# M121X.net
KiCad netlist of a schematic drawn in EAGLE
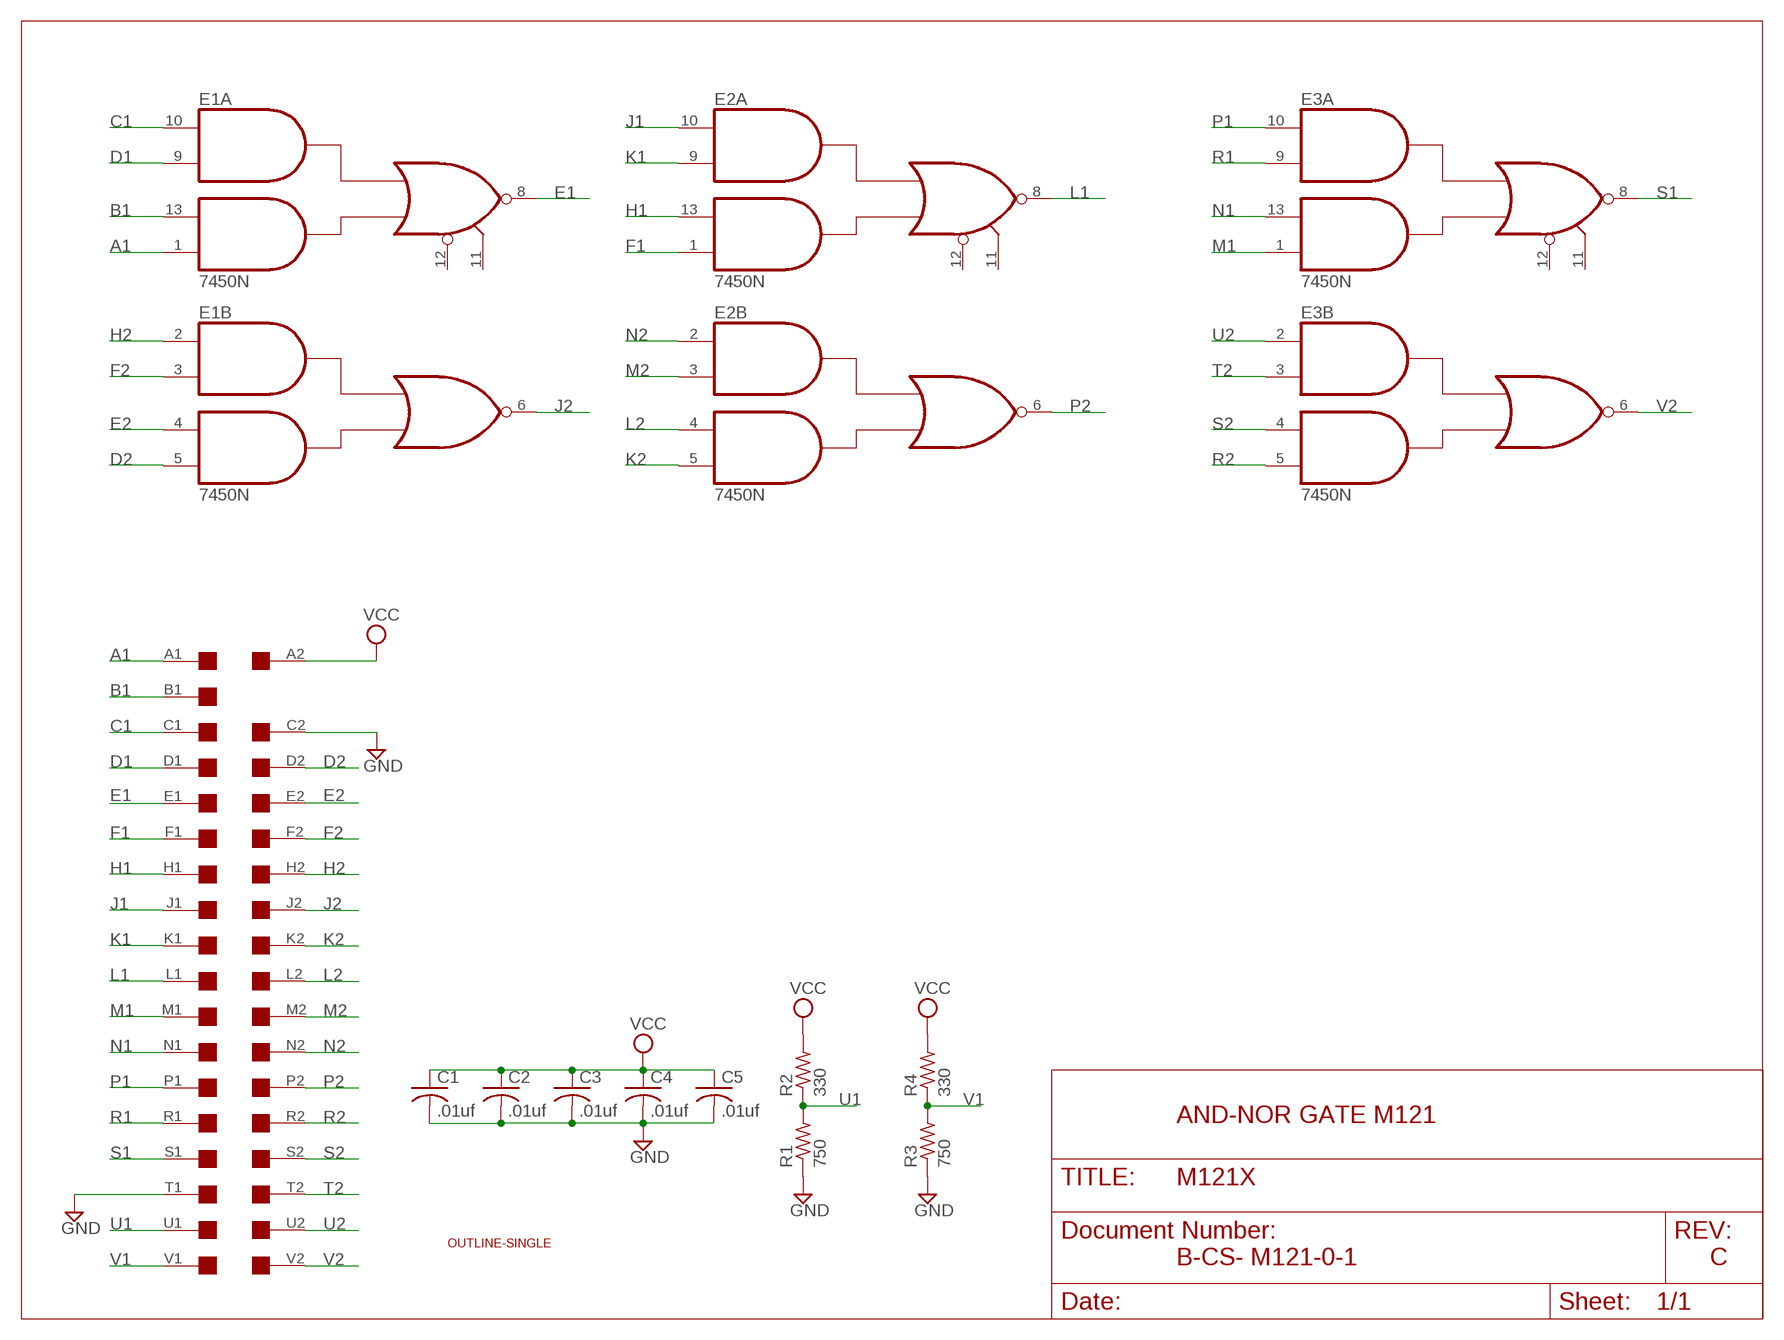
[diagram p0: schematic, sheet 1]

(export (version "E")
  (design (tool "Eeschema 10.0.6"))
  (components
    (comp (ref "C1")
      (value ".01uf")
      (footprint "eagle-import:C050-025X075")
      (libsource (lib "eagle-import") (part "C-US050-025X075"))
    )
    (comp (ref "C2")
      (value ".01uf")
      (footprint "eagle-import:C050-025X075")
      (libsource (lib "eagle-import") (part "C-US050-025X075"))
    )
    (comp (ref "C3")
      (value ".01uf")
      (footprint "eagle-import:C050-025X075")
      (libsource (lib "eagle-import") (part "C-US050-025X075"))
    )
    (comp (ref "C4")
      (value ".01uf")
      (footprint "eagle-import:C050-025X075")
      (libsource (lib "eagle-import") (part "C-US050-025X075"))
    )
    (comp (ref "C5")
      (value ".01uf")
      (footprint "eagle-import:C050-025X075")
      (libsource (lib "eagle-import") (part "C-US050-025X075"))
    )
    (comp (ref "E1")
      (value "7450N")
      (footprint "eagle-import:DIL14")
      (libsource (lib "eagle-import") (part "7450N"))
    )
    (comp (ref "E2")
      (value "7450N")
      (footprint "eagle-import:DIL14")
      (libsource (lib "eagle-import") (part "7450N"))
    )
    (comp (ref "E3")
      (value "7450N")
      (footprint "eagle-import:DIL14")
      (libsource (lib "eagle-import") (part "7450N"))
    )
    (comp (ref "R1")
      (value "750")
      (footprint "eagle-import:0207_10")
      (libsource (lib "eagle-import") (part "R-US_0207/10"))
    )
    (comp (ref "R2")
      (value "330")
      (footprint "eagle-import:0207_10")
      (libsource (lib "eagle-import") (part "R-US_0207/10"))
    )
    (comp (ref "R3")
      (value "750")
      (footprint "eagle-import:0207_10")
      (libsource (lib "eagle-import") (part "R-US_0207/10"))
    )
    (comp (ref "R4")
      (value "330")
      (footprint "eagle-import:0207_10")
      (libsource (lib "eagle-import") (part "R-US_0207/10"))
    )
    (comp (ref "U$1")
      (value "OUTLINE-SINGLE")
      (footprint "eagle-import:SINGLE")
      (libsource (lib "eagle-import") (part "OUTLINE-SINGLE"))
    )
    (comp (ref "U$4")
      (value "SINGLE")
      (footprint "eagle-import:EDGE-CON2")
      (libsource (lib "eagle-import") (part "SINGLE"))
    )
  )
  (nets
    (net (code "1") (name "/A1") (class "Default")
      (node (ref "E1") (pin "1") (pinfunction "I4_1") (pintype "input"))
      (node (ref "U$4") (pin "A1") (pinfunction "1_A1") (pintype "bidirectional"))
    )
    (net (code "2") (name "/B1") (class "Default")
      (node (ref "E1") (pin "13") (pinfunction "I3_13") (pintype "input"))
      (node (ref "U$4") (pin "B1") (pinfunction "1_B1") (pintype "bidirectional"))
    )
    (net (code "3") (name "/C1") (class "Default")
      (node (ref "E1") (pin "10") (pinfunction "I1_10") (pintype "input"))
      (node (ref "U$4") (pin "C1") (pinfunction "1_C1") (pintype "bidirectional"))
    )
    (net (code "4") (name "/D1") (class "Default")
      (node (ref "E1") (pin "9") (pinfunction "I2_9") (pintype "input"))
      (node (ref "U$4") (pin "D1") (pinfunction "1_D1") (pintype "bidirectional"))
    )
    (net (code "5") (name "/D2") (class "Default")
      (node (ref "E1") (pin "5") (pinfunction "I4_5") (pintype "input"))
      (node (ref "U$4") (pin "D2") (pinfunction "1_D2") (pintype "bidirectional"))
    )
    (net (code "6") (name "/E1") (class "Default")
      (node (ref "E1") (pin "8") (pinfunction "O_8") (pintype "output"))
      (node (ref "U$4") (pin "E1") (pinfunction "1_E1") (pintype "bidirectional"))
    )
    (net (code "7") (name "/E2") (class "Default")
      (node (ref "E1") (pin "4") (pinfunction "I3_4") (pintype "input"))
      (node (ref "U$4") (pin "E2") (pinfunction "1_E2") (pintype "bidirectional"))
    )
    (net (code "8") (name "/F1") (class "Default")
      (node (ref "E2") (pin "1") (pinfunction "I4_1") (pintype "input"))
      (node (ref "U$4") (pin "F1") (pinfunction "1_F1") (pintype "bidirectional"))
    )
    (net (code "9") (name "/F2") (class "Default")
      (node (ref "E1") (pin "3") (pinfunction "I2_3") (pintype "input"))
      (node (ref "U$4") (pin "F2") (pinfunction "1_F2") (pintype "bidirectional"))
    )
    (net (code "10") (name "/H1") (class "Default")
      (node (ref "E2") (pin "13") (pinfunction "I3_13") (pintype "input"))
      (node (ref "U$4") (pin "H1") (pinfunction "1_H1") (pintype "bidirectional"))
    )
    (net (code "11") (name "/H2") (class "Default")
      (node (ref "E1") (pin "2") (pinfunction "I1_2") (pintype "input"))
      (node (ref "U$4") (pin "H2") (pinfunction "1_H2") (pintype "bidirectional"))
    )
    (net (code "12") (name "/J1") (class "Default")
      (node (ref "E2") (pin "10") (pinfunction "I1_10") (pintype "input"))
      (node (ref "U$4") (pin "J1") (pinfunction "1_J1") (pintype "bidirectional"))
    )
    (net (code "13") (name "/J2") (class "Default")
      (node (ref "E1") (pin "6") (pinfunction "O_6") (pintype "output"))
      (node (ref "U$4") (pin "J2") (pinfunction "1_J2") (pintype "bidirectional"))
    )
    (net (code "14") (name "/K1") (class "Default")
      (node (ref "E2") (pin "9") (pinfunction "I2_9") (pintype "input"))
      (node (ref "U$4") (pin "K1") (pinfunction "1_K1") (pintype "bidirectional"))
    )
    (net (code "15") (name "/K2") (class "Default")
      (node (ref "E2") (pin "5") (pinfunction "I4_5") (pintype "input"))
      (node (ref "U$4") (pin "K2") (pinfunction "1_K2") (pintype "bidirectional"))
    )
    (net (code "16") (name "/L1") (class "Default")
      (node (ref "E2") (pin "8") (pinfunction "O_8") (pintype "output"))
      (node (ref "U$4") (pin "L1") (pinfunction "1_L1") (pintype "bidirectional"))
    )
    (net (code "17") (name "/L2") (class "Default")
      (node (ref "E2") (pin "4") (pinfunction "I3_4") (pintype "input"))
      (node (ref "U$4") (pin "L2") (pinfunction "1_L2") (pintype "bidirectional"))
    )
    (net (code "18") (name "/M1") (class "Default")
      (node (ref "E3") (pin "1") (pinfunction "I4_1") (pintype "input"))
      (node (ref "U$4") (pin "M1") (pinfunction "1_M1") (pintype "bidirectional"))
    )
    (net (code "19") (name "/M2") (class "Default")
      (node (ref "E2") (pin "3") (pinfunction "I2_3") (pintype "input"))
      (node (ref "U$4") (pin "M2") (pinfunction "1_M2") (pintype "bidirectional"))
    )
    (net (code "20") (name "/N1") (class "Default")
      (node (ref "E3") (pin "13") (pinfunction "I3_13") (pintype "input"))
      (node (ref "U$4") (pin "N1") (pinfunction "1_N1") (pintype "bidirectional"))
    )
    (net (code "21") (name "/N2") (class "Default")
      (node (ref "E2") (pin "2") (pinfunction "I1_2") (pintype "input"))
      (node (ref "U$4") (pin "N2") (pinfunction "1_N2") (pintype "bidirectional"))
    )
    (net (code "22") (name "/P1") (class "Default")
      (node (ref "E3") (pin "10") (pinfunction "I1_10") (pintype "input"))
      (node (ref "U$4") (pin "P1") (pinfunction "1_P1") (pintype "bidirectional"))
    )
    (net (code "23") (name "/P2") (class "Default")
      (node (ref "E2") (pin "6") (pinfunction "O_6") (pintype "output"))
      (node (ref "U$4") (pin "P2") (pinfunction "1_P2") (pintype "bidirectional"))
    )
    (net (code "24") (name "/R1") (class "Default")
      (node (ref "E3") (pin "9") (pinfunction "I2_9") (pintype "input"))
      (node (ref "U$4") (pin "R1") (pinfunction "1_R1") (pintype "bidirectional"))
    )
    (net (code "25") (name "/R2") (class "Default")
      (node (ref "E3") (pin "5") (pinfunction "I4_5") (pintype "input"))
      (node (ref "U$4") (pin "R2") (pinfunction "1_R2") (pintype "bidirectional"))
    )
    (net (code "26") (name "/S1") (class "Default")
      (node (ref "E3") (pin "8") (pinfunction "O_8") (pintype "output"))
      (node (ref "U$4") (pin "S1") (pinfunction "1_S1") (pintype "bidirectional"))
    )
    (net (code "27") (name "/S2") (class "Default")
      (node (ref "E3") (pin "4") (pinfunction "I3_4") (pintype "input"))
      (node (ref "U$4") (pin "S2") (pinfunction "1_S2") (pintype "bidirectional"))
    )
    (net (code "28") (name "/T2") (class "Default")
      (node (ref "E3") (pin "3") (pinfunction "I2_3") (pintype "input"))
      (node (ref "U$4") (pin "T2") (pinfunction "1_T2") (pintype "bidirectional"))
    )
    (net (code "29") (name "/U1") (class "Default")
      (node (ref "R1") (pin "2") (pinfunction "2_2") (pintype "passive"))
      (node (ref "R2") (pin "1") (pinfunction "1_1") (pintype "passive"))
      (node (ref "U$4") (pin "U1") (pinfunction "1_U1") (pintype "bidirectional"))
    )
    (net (code "30") (name "/U2") (class "Default")
      (node (ref "E3") (pin "2") (pinfunction "I1_2") (pintype "input"))
      (node (ref "U$4") (pin "U2") (pinfunction "1_U2") (pintype "bidirectional"))
    )
    (net (code "31") (name "/V1") (class "Default")
      (node (ref "R3") (pin "2") (pinfunction "2_2") (pintype "passive"))
      (node (ref "R4") (pin "1") (pinfunction "1_1") (pintype "passive"))
      (node (ref "U$4") (pin "V1") (pinfunction "1_V1") (pintype "bidirectional"))
    )
    (net (code "32") (name "/V2") (class "Default")
      (node (ref "E3") (pin "6") (pinfunction "O_6") (pintype "output"))
      (node (ref "U$4") (pin "V2") (pinfunction "1_V2") (pintype "bidirectional"))
    )
    (net (code "33") (name "GND") (class "Default")
      (node (ref "C1") (pin "2") (pinfunction "2_2") (pintype "passive"))
      (node (ref "C2") (pin "2") (pinfunction "2_2") (pintype "passive"))
      (node (ref "C3") (pin "2") (pinfunction "2_2") (pintype "passive"))
      (node (ref "C4") (pin "2") (pinfunction "2_2") (pintype "passive"))
      (node (ref "C5") (pin "2") (pinfunction "2_2") (pintype "passive"))
      (node (ref "R1") (pin "1") (pinfunction "1_1") (pintype "passive"))
      (node (ref "R3") (pin "1") (pinfunction "1_1") (pintype "passive"))
      (node (ref "U$4") (pin "C2") (pinfunction "1_C2") (pintype "bidirectional"))
      (node (ref "U$4") (pin "T1") (pinfunction "1_T1") (pintype "bidirectional"))
    )
    (net (code "34") (name "VCC") (class "Default")
      (node (ref "C1") (pin "1") (pinfunction "1_1") (pintype "passive"))
      (node (ref "C2") (pin "1") (pinfunction "1_1") (pintype "passive"))
      (node (ref "C3") (pin "1") (pinfunction "1_1") (pintype "passive"))
      (node (ref "C4") (pin "1") (pinfunction "1_1") (pintype "passive"))
      (node (ref "C5") (pin "1") (pinfunction "1_1") (pintype "passive"))
      (node (ref "R2") (pin "2") (pinfunction "2_2") (pintype "passive"))
      (node (ref "R4") (pin "2") (pinfunction "2_2") (pintype "passive"))
      (node (ref "U$4") (pin "A2") (pinfunction "1_A2") (pintype "bidirectional"))
    )
    (net (code "35") (name "unconnected-(E1A-I5-Pad12)") (class "Default")
      (node (ref "E1") (pin "12") (pinfunction "I5_12") (pintype "passive"))
    )
    (net (code "36") (name "unconnected-(E1A-I6-Pad11)") (class "Default")
      (node (ref "E1") (pin "11") (pinfunction "I6_11") (pintype "passive"))
    )
    (net (code "37") (name "unconnected-(E2A-I5-Pad12)") (class "Default")
      (node (ref "E2") (pin "12") (pinfunction "I5_12") (pintype "passive"))
    )
    (net (code "38") (name "unconnected-(E2A-I6-Pad11)") (class "Default")
      (node (ref "E2") (pin "11") (pinfunction "I6_11") (pintype "passive"))
    )
    (net (code "39") (name "unconnected-(E3A-I5-Pad12)") (class "Default")
      (node (ref "E3") (pin "12") (pinfunction "I5_12") (pintype "passive"))
    )
    (net (code "40") (name "unconnected-(E3A-I6-Pad11)") (class "Default")
      (node (ref "E3") (pin "11") (pinfunction "I6_11") (pintype "passive"))
    )
  )
)
